# Power_Supplies.net
KiCad netlist of a schematic drawn in Altium Designer
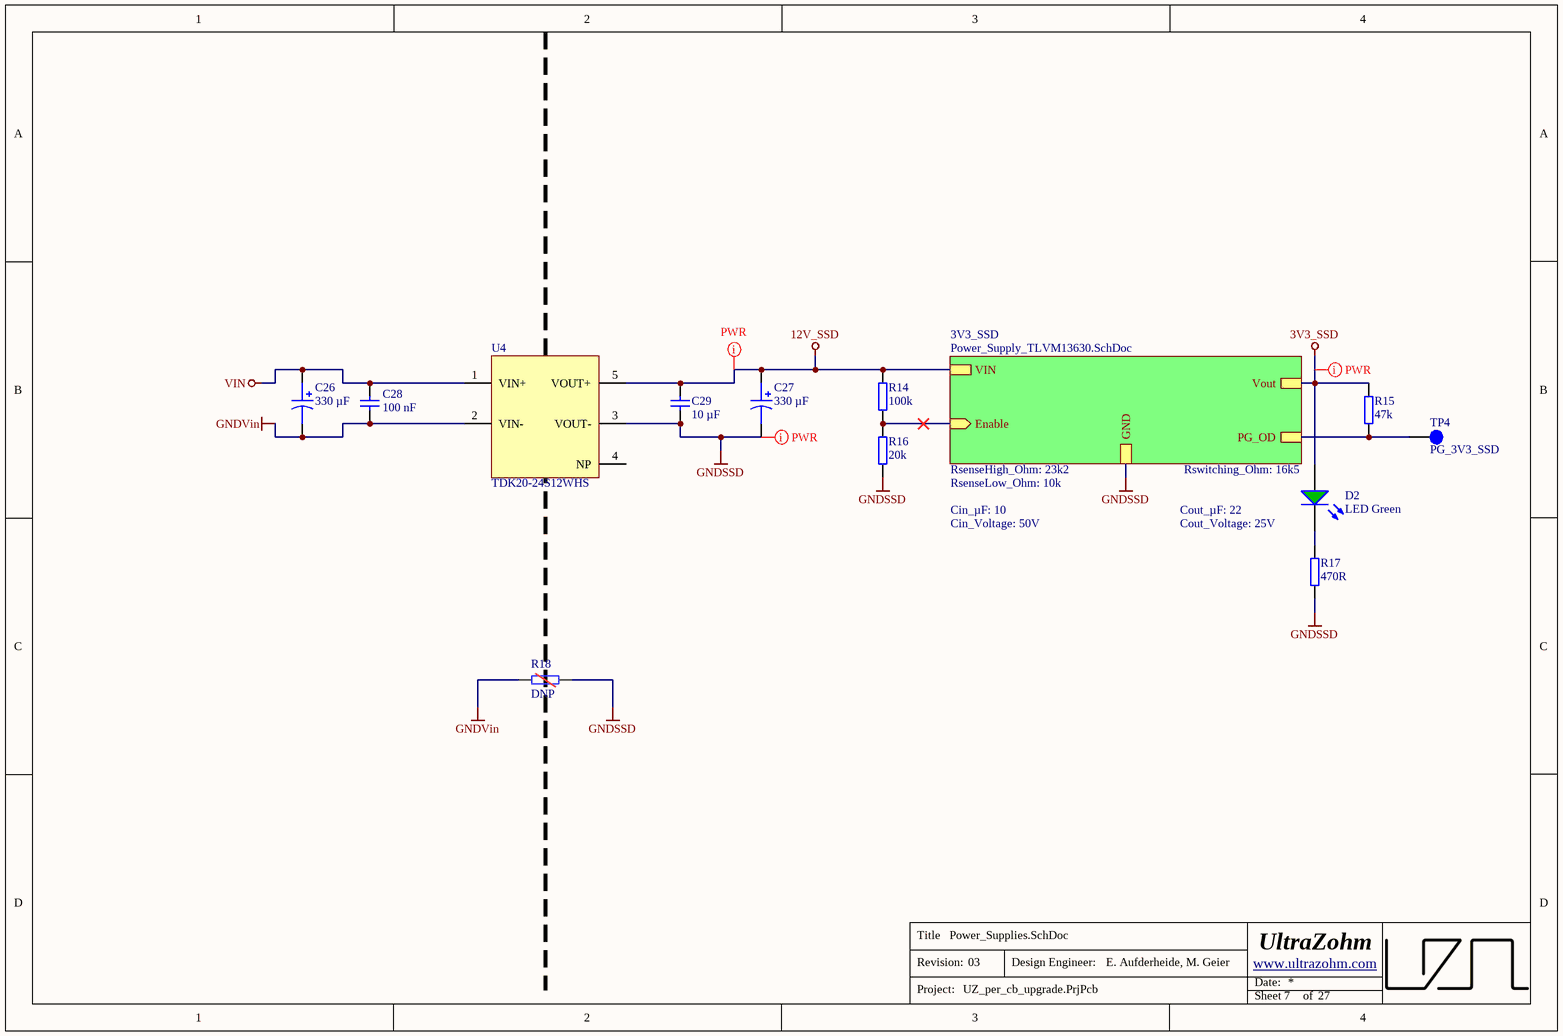
[diagram p0: Power_Supplies.SchDoc]

(export (version "E")
  (design (tool "Eeschema 10.0.6"))
  (components
    (comp (ref "C26")
      (value "330 µF")
      (footprint "SM_RADIAL_10mm")
      (description "Aluminium Electrolytic Capacitors - SMD 330uF 50V")
      (fields
        (field (name "MANUFACTURER PART NUMBER") "EEEFT1H331GP")
        (field (name "MANUFACTURER") "Panasonic")
        (field (name "CREATED FROM") "FRosner")
      )
      (libsource (lib "user") (part "CAPACITOR_POLARIZED_EEE"))
    )
    (comp (ref "C27")
      (value "330 µF")
      (footprint "SM_RADIAL_10mm")
      (description "Aluminium Electrolytic Capacitors - SMD 330uF 50V")
      (fields
        (field (name "MANUFACTURER PART NUMBER") "EEEFT1H331GP")
        (field (name "MANUFACTURER") "Panasonic")
        (field (name "CREATED FROM") "FRosner")
      )
      (libsource (lib "user") (part "CAPACITOR_POLARIZED_EEE"))
    )
    (comp (ref "C28")
      (value "100 nF")
      (footprint "C_0603_TE")
      (description "Generic capacitor")
      (fields
        (field (name "TOLERANCE") "10 %")
        (field (name "MANUFACTURER PART NUMBER") "UZgen_C_0603_100nF_50V_X7R")
        (field (name "CREATED FROM") "AGeiger")
      )
      (libsource (lib "user") (part "CAP-NP"))
    )
    (comp (ref "C29")
      (value "10 µF")
      (footprint "C_1206_TE")
      (description "Generic capacitor")
      (fields
        (field (name "MANUFACTURER PART NUMBER") "UZgen_C_1206_10uF_50V_X7R")
        (field (name "MANUFACTURER") "UZgen")
        (field (name "CREATED FROM") "MGeier")
      )
      (libsource (lib "user") (part "CAP-NP"))
    )
    (comp (ref "D2")
      (value "LED Green")
      (footprint "WL-SMCW_0603")
      (description "Standard LEDs - SMD 0603 green")
      (fields
        (field (name "MANUFACTURER PART NUMBER") "UZgen_LED_0603_Green")
        (field (name "MANUFACTURER") "UZgen")
        (field (name "CREATED FROM") "UZgenTool")
      )
      (libsource (lib "user") (part "LED_Green"))
    )
    (comp (ref "R14")
      (value "100k")
      (footprint "R_0603_TE")
      (description "Generic resistor")
      (fields
        (field (name "MANUFACTURER PART NUMBER") "UZgen_R_0603_100k")
        (field (name "MANUFACTURER") "UZgen")
        (field (name "CREATED FROM") "UZgenTool")
      )
      (libsource (lib "user") (part "RES"))
    )
    (comp (ref "R15")
      (value "47k")
      (footprint "R_0603_TE")
      (description "Generic resistor")
      (fields
        (field (name "MANUFACTURER PART NUMBER") "UZgen_R_0603_47k")
        (field (name "MANUFACTURER") "UZgen")
        (field (name "CREATED FROM") "UZgenTool")
      )
      (libsource (lib "user") (part "RES"))
    )
    (comp (ref "R16")
      (value "20k")
      (footprint "R_0603_TE")
      (description "Generic resistor")
      (fields
        (field (name "MANUFACTURER PART NUMBER") "UZgen_R_0603_20k")
        (field (name "MANUFACTURER") "UZgen")
        (field (name "CREATED FROM") "UZgenTool")
      )
      (libsource (lib "user") (part "RES"))
    )
    (comp (ref "R17")
      (value "470R")
      (footprint "R_0603_TE")
      (description "Generic resistor")
      (fields
        (field (name "MANUFACTURER PART NUMBER") "UZgen_R_0603_470R")
        (field (name "MANUFACTURER") "UZgen")
        (field (name "CREATED FROM") "UZgenTool")
      )
      (libsource (lib "user") (part "RES"))
    )
    (comp (ref "R18")
      (value "DNP")
      (footprint "R_1206_TE-DNP")
      (description "Generic resistor (DNP)")
      (fields
        (field (name "MANUFACTURER PART NUMBER") "UZgen_R_1206_DNP")
        (field (name "MANUFACTURER") "UZgen")
        (field (name "CREATED FROM") "UZgenTool")
      )
      (libsource (lib "user") (part "RES-DNP"))
    )
    (comp (ref "TP4")
      (value "PG_3V3_SSD")
      (footprint "TP_1mm")
      (description "Testpoint 1mm")
      (fields
        (field (name "MANUFACTURER PART NUMBER") "NULL")
        (field (name "CREATED") "2018_06_25_AGeiger")
        (field (name "CREATED FROM") "AGeiger")
      )
      (libsource (lib "user") (part "TP_1mm"))
    )
    (comp (ref "U4")
      (value "TDK20-24S12WHS")
      (footprint "TDKxx-yySzzS_25.4x25.4")
      (description "9-36V to 12V 1.67A / Plugin,25.4x25.4mm Isolated Power Modules ROHS")
      (fields
        (field (name "MANUFACTURER") "TDPOWER")
        (field (name "LCSC PART NUMBER") "C7494352")
        (field (name "CREATED FROM") "MGeier")
      )
      (libsource (lib "user") (part "TDKxx-yySzzS"))
    )
  )
  (nets
    (net (code "1") (name "/Enable") (class "Default")
      (node (ref "R14") (pin "1") (pinfunction "1_1") (pintype "passive"))
      (node (ref "R16") (pin "2") (pinfunction "2_2") (pintype "passive"))
    )
    (net (code "2") (name "/PG_OD") (class "Default")
      (node (ref "R15") (pin "2") (pinfunction "2_2") (pintype "passive"))
      (node (ref "TP4") (pin "1") (pintype "passive"))
    )
    (net (code "3") (name "3V3_SSD") (class "Default")
      (node (ref "D2") (pin "2") (pinfunction "A_2") (pintype "passive"))
      (node (ref "R15") (pin "1") (pinfunction "1_1") (pintype "passive"))
    )
    (net (code "4") (name "12V_SSD") (class "Default")
      (node (ref "C27") (pin "1") (pinfunction "1_1") (pintype "passive"))
      (node (ref "C29") (pin "2") (pinfunction "2_2") (pintype "passive"))
      (node (ref "R14") (pin "2") (pinfunction "2_2") (pintype "passive"))
      (node (ref "U4") (pin "5") (pinfunction "VOUT+_5") (pintype "power_in"))
    )
    (net (code "5") (name "GNDSSD") (class "Default")
      (node (ref "C27") (pin "2") (pinfunction "2_2") (pintype "passive"))
      (node (ref "C29") (pin "1") (pinfunction "1_1") (pintype "passive"))
      (node (ref "R16") (pin "1") (pinfunction "1_1") (pintype "passive"))
      (node (ref "R17") (pin "1") (pinfunction "1_1") (pintype "passive"))
      (node (ref "R18") (pin "1") (pinfunction "1_1") (pintype "passive"))
      (node (ref "U4") (pin "3") (pinfunction "VOUT-_3") (pintype "power_in"))
    )
    (net (code "6") (name "GNDVin") (class "Default")
      (node (ref "C26") (pin "2") (pinfunction "2_2") (pintype "passive"))
      (node (ref "C28") (pin "2") (pinfunction "2_2") (pintype "passive"))
      (node (ref "R18") (pin "2") (pinfunction "2_2") (pintype "passive"))
      (node (ref "U4") (pin "2") (pinfunction "VIN-_2") (pintype "power_in"))
    )
    (net (code "7") (name "Net-(D2-K)") (class "Default")
      (node (ref "D2") (pin "1") (pinfunction "K_1") (pintype "passive"))
      (node (ref "R17") (pin "2") (pinfunction "2_2") (pintype "passive"))
    )
    (net (code "8") (name "VIN") (class "Default")
      (node (ref "C26") (pin "1") (pinfunction "1_1") (pintype "passive"))
      (node (ref "C28") (pin "1") (pinfunction "1_1") (pintype "passive"))
      (node (ref "U4") (pin "1") (pinfunction "VIN+_1") (pintype "power_in"))
    )
    (net (code "9") (name "unconnected-(U4-NP-Pad4)") (class "Default")
      (node (ref "U4") (pin "4") (pinfunction "NP_4") (pintype "passive"))
    )
  )
)
